# main.net
KiCad netlist of a schematic drawn in EAGLE
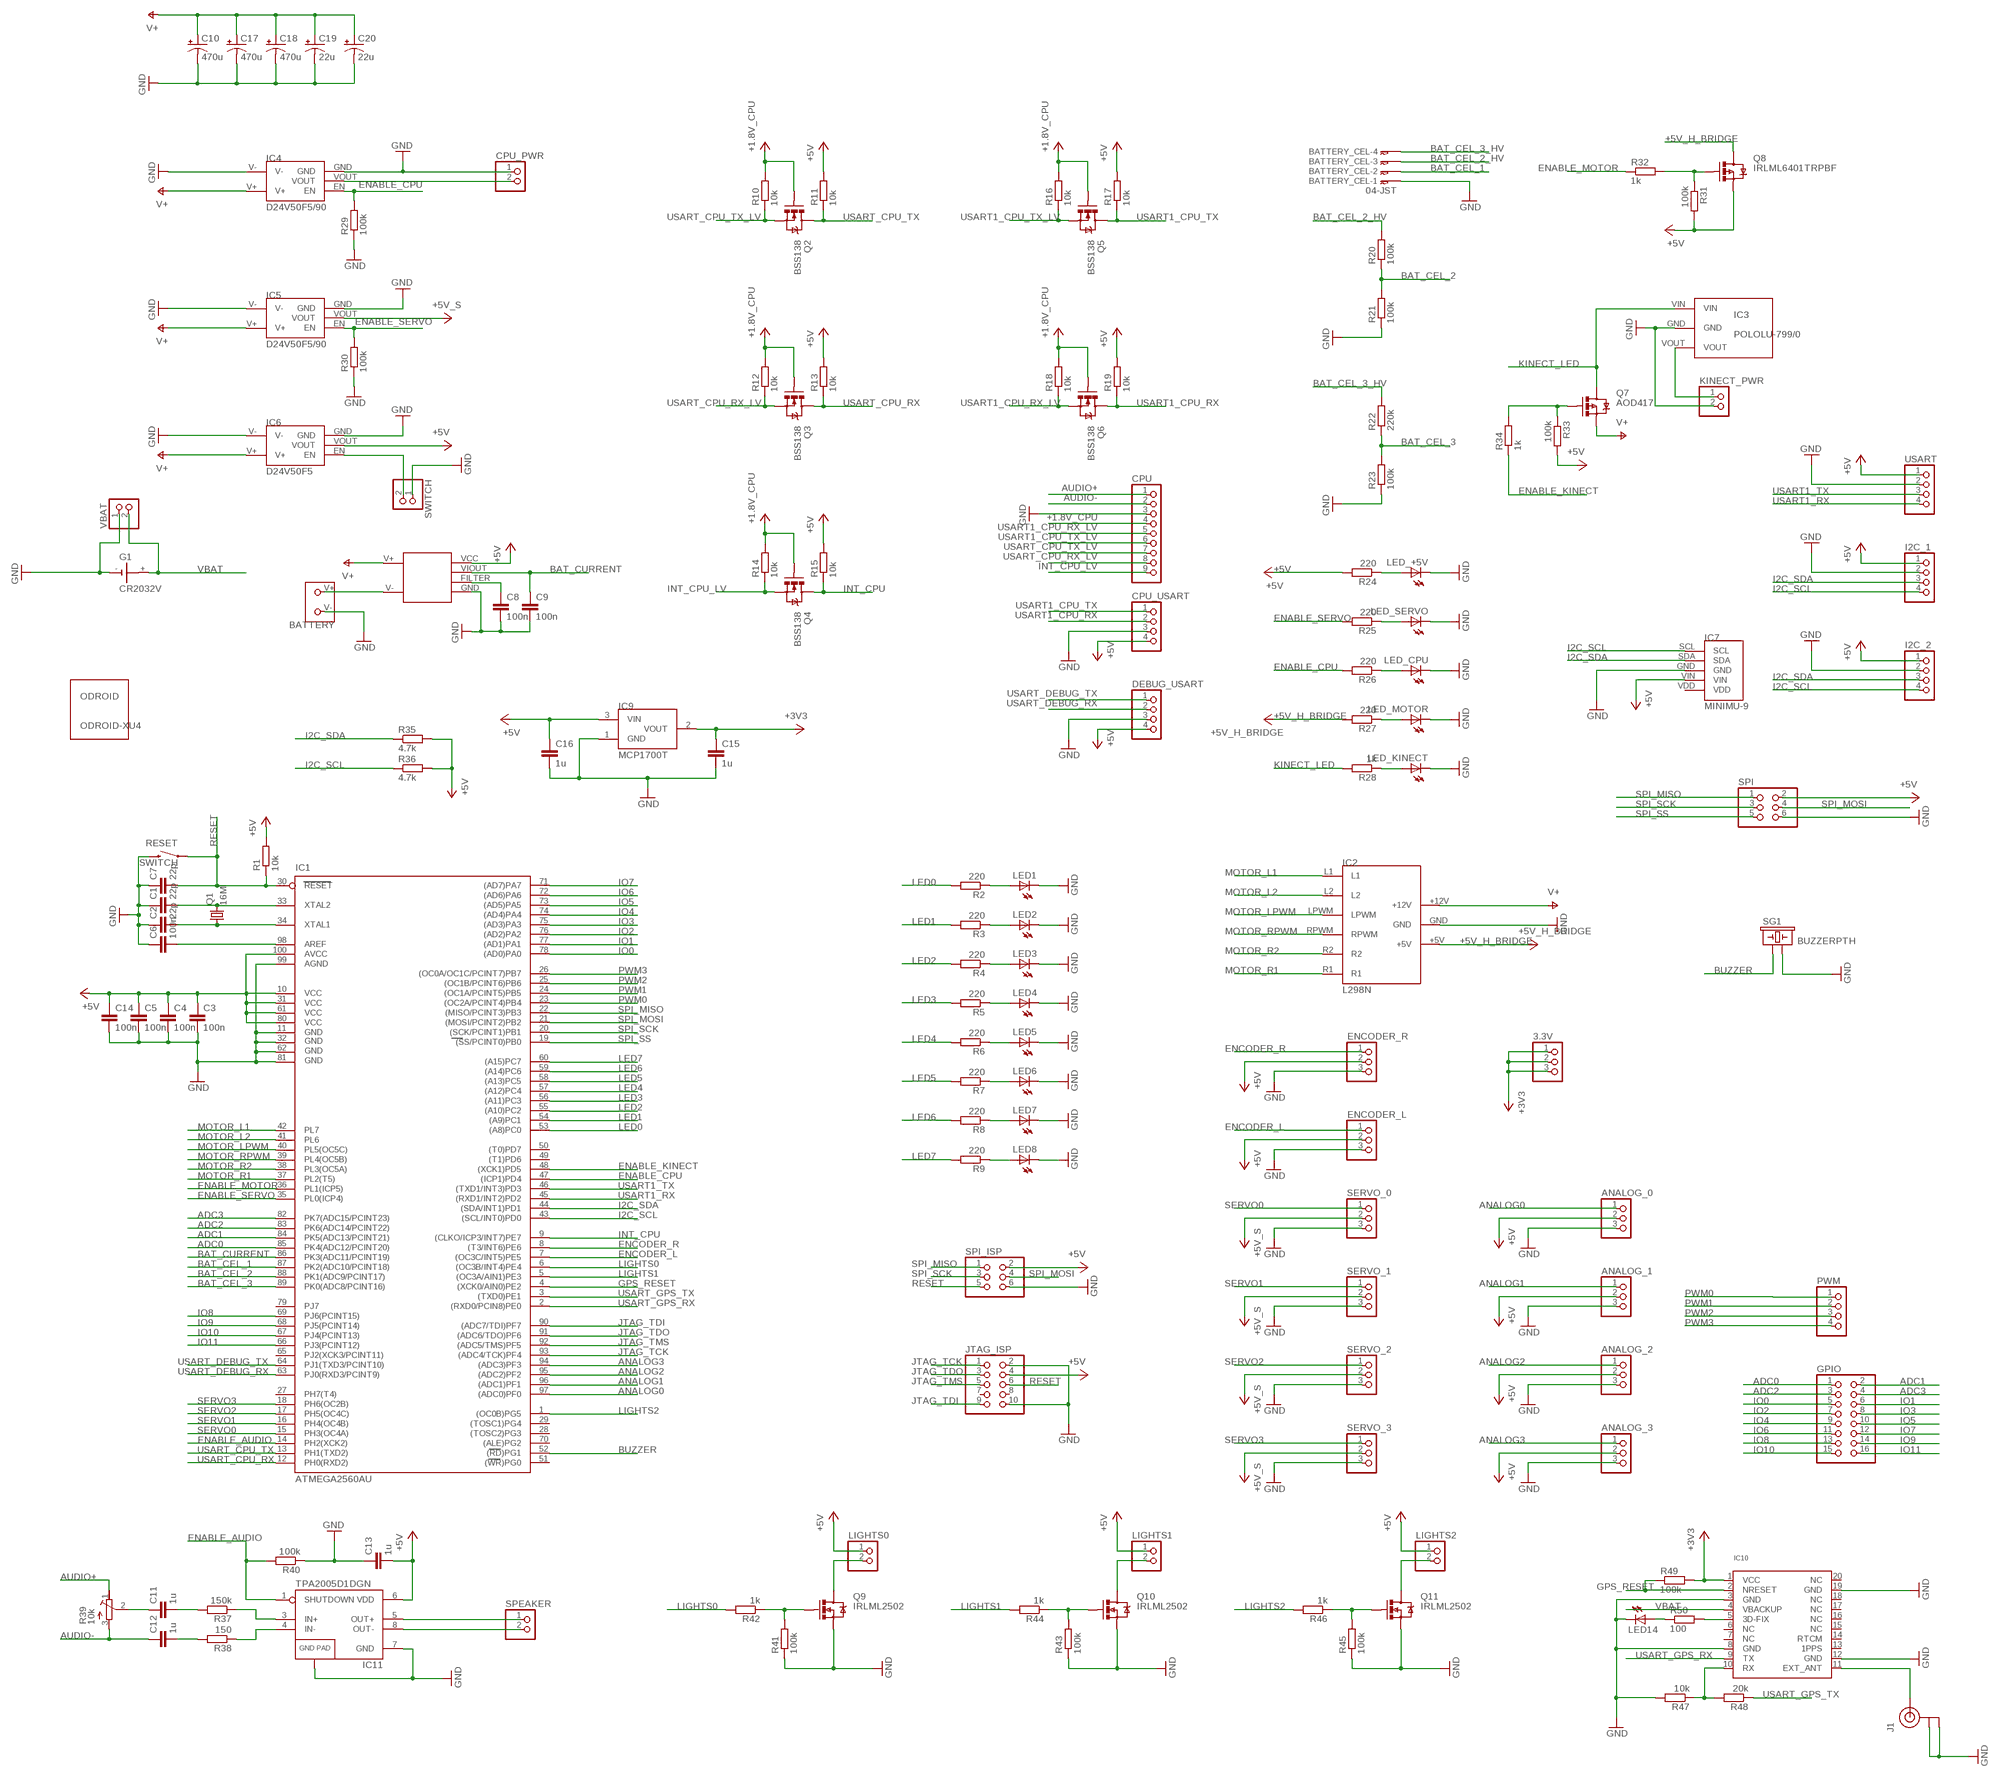
[diagram p0: schematic, sheet 1]

(export (version "E")
  (design (tool "Eeschema 10.0.6"))
  (components
    (comp (ref "3.3V")
      (value "PINHD-1X3")
      (footprint "eagle-import:1X03")
      (libsource (lib "eagle-import") (part "PINHD-1X3"))
    )
    (comp (ref "ANALOG_0")
      (value "PINHD-1X3")
      (footprint "eagle-import:1X03")
      (libsource (lib "eagle-import") (part "PINHD-1X3"))
    )
    (comp (ref "ANALOG_1")
      (value "PINHD-1X3")
      (footprint "eagle-import:1X03")
      (libsource (lib "eagle-import") (part "PINHD-1X3"))
    )
    (comp (ref "ANALOG_2")
      (value "PINHD-1X3")
      (footprint "eagle-import:1X03")
      (libsource (lib "eagle-import") (part "PINHD-1X3"))
    )
    (comp (ref "ANALOG_3")
      (value "PINHD-1X3")
      (footprint "eagle-import:1X03")
      (libsource (lib "eagle-import") (part "PINHD-1X3"))
    )
    (comp (ref "BATTERY")
      (value "XT60")
      (footprint "eagle-import:XT60")
      (libsource (lib "eagle-import") (part "XT60"))
    )
    (comp (ref "BATTERY_CEL")
      (value "04-JST")
      (footprint "eagle-import:B4B-XH")
      (libsource (lib "eagle-import") (part "04-JST-B4B-XH-A"))
    )
    (comp (ref "C1")
      (value "22p")
      (footprint "eagle-import:C0805")
      (libsource (lib "eagle-import") (part "C-EUC0805"))
    )
    (comp (ref "C2")
      (value "22p")
      (footprint "eagle-import:C0805")
      (libsource (lib "eagle-import") (part "C-EUC0805"))
    )
    (comp (ref "C3")
      (value "100n")
      (footprint "eagle-import:C0805")
      (libsource (lib "eagle-import") (part "C-EUC0805"))
    )
    (comp (ref "C4")
      (value "100n")
      (footprint "eagle-import:C0805")
      (libsource (lib "eagle-import") (part "C-EUC0805"))
    )
    (comp (ref "C5")
      (value "100n")
      (footprint "eagle-import:C0805")
      (libsource (lib "eagle-import") (part "C-EUC0805"))
    )
    (comp (ref "C6")
      (value "100n")
      (footprint "eagle-import:C0805")
      (libsource (lib "eagle-import") (part "C-EUC0805"))
    )
    (comp (ref "C7")
      (value "22p")
      (footprint "eagle-import:C0805")
      (libsource (lib "eagle-import") (part "C-EUC0805"))
    )
    (comp (ref "C8")
      (value "100n")
      (footprint "eagle-import:C0805")
      (libsource (lib "eagle-import") (part "C-EUC0805"))
    )
    (comp (ref "C9")
      (value "100n")
      (footprint "eagle-import:C0805")
      (libsource (lib "eagle-import") (part "C-EUC0805"))
    )
    (comp (ref "C10")
      (value "470u")
      (footprint "eagle-import:PANASONIC_G")
      (libsource (lib "eagle-import") (part "CAP_POLG"))
    )
    (comp (ref "C11")
      (value "1u")
      (footprint "eagle-import:C0805")
      (libsource (lib "eagle-import") (part "C-EUC0805"))
    )
    (comp (ref "C12")
      (value "1u")
      (footprint "eagle-import:C0805")
      (libsource (lib "eagle-import") (part "C-EUC0805"))
    )
    (comp (ref "C13")
      (value "1u")
      (footprint "eagle-import:C0805")
      (libsource (lib "eagle-import") (part "C-EUC0805"))
    )
    (comp (ref "C14")
      (value "100n")
      (footprint "eagle-import:C0805")
      (libsource (lib "eagle-import") (part "C-EUC0805"))
    )
    (comp (ref "C15")
      (value "1u")
      (footprint "eagle-import:C0805")
      (libsource (lib "eagle-import") (part "C-EUC0805"))
    )
    (comp (ref "C16")
      (value "1u")
      (footprint "eagle-import:C0805")
      (libsource (lib "eagle-import") (part "C-EUC0805"))
    )
    (comp (ref "C17")
      (value "470u")
      (footprint "eagle-import:PANASONIC_G")
      (libsource (lib "eagle-import") (part "CAP_POLG"))
    )
    (comp (ref "C18")
      (value "470u")
      (footprint "eagle-import:PANASONIC_G")
      (libsource (lib "eagle-import") (part "CAP_POLG"))
    )
    (comp (ref "C19")
      (value "22u")
      (footprint "eagle-import:EIA6032")
      (libsource (lib "eagle-import") (part "SparkFun-Passives_CAP_POL6032"))
    )
    (comp (ref "C20")
      (value "22u")
      (footprint "eagle-import:EIA6032")
      (libsource (lib "eagle-import") (part "SparkFun-Passives_CAP_POL6032"))
    )
    (comp (ref "CPU")
      (value "PINHD-1X9")
      (footprint "eagle-import:1X09")
      (libsource (lib "eagle-import") (part "PINHD-1X9"))
    )
    (comp (ref "CPU_PWR")
      (value "PINHD-1X2")
      (footprint "eagle-import:1X02")
      (libsource (lib "eagle-import") (part "PINHD-1X2"))
    )
    (comp (ref "CPU_USART")
      (value "PINHD-1X4/90")
      (footprint "eagle-import:1X04_90")
      (libsource (lib "eagle-import") (part "PINHD-1X4/90"))
    )
    (comp (ref "DEBUG_USART")
      (value "PINHD-1X4/90")
      (footprint "eagle-import:1X04_90")
      (libsource (lib "eagle-import") (part "PINHD-1X4/90"))
    )
    (comp (ref "ENCODER_L")
      (value "PINHD-1X3")
      (footprint "eagle-import:1X03")
      (libsource (lib "eagle-import") (part "PINHD-1X3"))
    )
    (comp (ref "ENCODER_R")
      (value "PINHD-1X3")
      (footprint "eagle-import:1X03")
      (libsource (lib "eagle-import") (part "PINHD-1X3"))
    )
    (comp (ref "G1")
      (value "CR2032V")
      (footprint "eagle-import:CR2032V")
      (libsource (lib "eagle-import") (part "CR2032V"))
    )
    (comp (ref "GPIO")
      (value "PINHD-2X8")
      (footprint "eagle-import:2X08")
      (libsource (lib "eagle-import") (part "PINHD-2X8"))
    )
    (comp (ref "I2C_1")
      (value "PINHD-1X4")
      (footprint "eagle-import:1X04")
      (libsource (lib "eagle-import") (part "PINHD-1X4"))
    )
    (comp (ref "I2C_2")
      (value "PINHD-1X4")
      (footprint "eagle-import:1X04")
      (libsource (lib "eagle-import") (part "PINHD-1X4"))
    )
    (comp (ref "IC1")
      (value "ATMEGA2560AU")
      (footprint "eagle-import:TQFP100")
      (libsource (lib "eagle-import") (part "ATMEGA2560AU"))
    )
    (comp (ref "IC2")
      (value "L298N")
      (footprint "eagle-import:L298N-MOD")
      (libsource (lib "eagle-import") (part "L298N"))
    )
    (comp (ref "IC3")
      (value "POLOLU-799/0")
      (footprint "eagle-import:POLOLU799_0")
      (libsource (lib "eagle-import") (part "POLOLU-799/0"))
    )
    (comp (ref "IC4")
      (value "D24V50F5/90")
      (footprint "eagle-import:D24V50_90")
      (libsource (lib "eagle-import") (part "D24V50F5/90"))
    )
    (comp (ref "IC5")
      (value "D24V50F5/90")
      (footprint "eagle-import:D24V50_90")
      (libsource (lib "eagle-import") (part "D24V50F5/90"))
    )
    (comp (ref "IC6")
      (value "D24V50F5")
      (footprint "eagle-import:D24V50")
      (libsource (lib "eagle-import") (part "D24V50F5"))
    )
    (comp (ref "IC7")
      (value "MINIMU-9")
      (footprint "eagle-import:MINIMU-9_V3")
      (libsource (lib "eagle-import") (part "MINIMU-9"))
    )
    (comp (ref "IC8")
      (value "ACS715")
      (footprint "eagle-import:ACS71X")
      (libsource (lib "eagle-import") (part "ACS715"))
    )
    (comp (ref "IC9")
      (value "MCP1700T")
      (footprint "eagle-import:SOT23")
      (libsource (lib "eagle-import") (part "MCP1700T"))
    )
    (comp (ref "IC10")
      (value "GPS_FGPMMOPA6H")
      (footprint "eagle-import:FGPMMOPA6H")
      (libsource (lib "eagle-import") (part "GPS_FGPMMOPA6H"))
    )
    (comp (ref "IC11")
      (value "TPA2005D1DGN")
      (footprint "eagle-import:POWER-SOP8")
      (libsource (lib "eagle-import") (part "TPA2005D1DGN"))
    )
    (comp (ref "J1")
      (value "U.FL")
      (footprint "eagle-import:U.FL")
      (libsource (lib "eagle-import") (part "U.FL"))
    )
    (comp (ref "JTAG_ISP")
      (value "PINHD-2X5/90")
      (footprint "eagle-import:2X05_90")
      (libsource (lib "eagle-import") (part "PINHD-2X5/90"))
    )
    (comp (ref "KINECT_PWR")
      (value "PINHD-1X2")
      (footprint "eagle-import:1X02")
      (libsource (lib "eagle-import") (part "PINHD-1X2"))
    )
    (comp (ref "LED1")
      (value "LEDCHIPLED_0805")
      (footprint "eagle-import:CHIPLED_0805")
      (libsource (lib "eagle-import") (part "LEDCHIPLED_0805"))
    )
    (comp (ref "LED2")
      (value "LEDCHIPLED_0805")
      (footprint "eagle-import:CHIPLED_0805")
      (libsource (lib "eagle-import") (part "LEDCHIPLED_0805"))
    )
    (comp (ref "LED3")
      (value "LEDCHIPLED_0805")
      (footprint "eagle-import:CHIPLED_0805")
      (libsource (lib "eagle-import") (part "LEDCHIPLED_0805"))
    )
    (comp (ref "LED4")
      (value "LEDCHIPLED_0805")
      (footprint "eagle-import:CHIPLED_0805")
      (libsource (lib "eagle-import") (part "LEDCHIPLED_0805"))
    )
    (comp (ref "LED5")
      (value "LEDCHIPLED_0805")
      (footprint "eagle-import:CHIPLED_0805")
      (libsource (lib "eagle-import") (part "LEDCHIPLED_0805"))
    )
    (comp (ref "LED6")
      (value "LEDCHIPLED_0805")
      (footprint "eagle-import:CHIPLED_0805")
      (libsource (lib "eagle-import") (part "LEDCHIPLED_0805"))
    )
    (comp (ref "LED7")
      (value "LEDCHIPLED_0805")
      (footprint "eagle-import:CHIPLED_0805")
      (libsource (lib "eagle-import") (part "LEDCHIPLED_0805"))
    )
    (comp (ref "LED8")
      (value "LEDCHIPLED_0805")
      (footprint "eagle-import:CHIPLED_0805")
      (libsource (lib "eagle-import") (part "LEDCHIPLED_0805"))
    )
    (comp (ref "LED14")
      (value "LEDCHIPLED_0805")
      (footprint "eagle-import:CHIPLED_0805")
      (libsource (lib "eagle-import") (part "LEDCHIPLED_0805"))
    )
    (comp (ref "LED_+5V")
      (value "LEDCHIPLED_0805")
      (footprint "eagle-import:CHIPLED_0805")
      (libsource (lib "eagle-import") (part "LEDCHIPLED_0805"))
    )
    (comp (ref "LED_CPU")
      (value "LEDCHIPLED_0805")
      (footprint "eagle-import:CHIPLED_0805")
      (libsource (lib "eagle-import") (part "LEDCHIPLED_0805"))
    )
    (comp (ref "LED_KINECT")
      (value "LEDCHIPLED_0805")
      (footprint "eagle-import:CHIPLED_0805")
      (libsource (lib "eagle-import") (part "LEDCHIPLED_0805"))
    )
    (comp (ref "LED_MOTOR")
      (value "LEDCHIPLED_0805")
      (footprint "eagle-import:CHIPLED_0805")
      (libsource (lib "eagle-import") (part "LEDCHIPLED_0805"))
    )
    (comp (ref "LED_SERVO")
      (value "LEDCHIPLED_0805")
      (footprint "eagle-import:CHIPLED_0805")
      (libsource (lib "eagle-import") (part "LEDCHIPLED_0805"))
    )
    (comp (ref "LIGHTS0")
      (value "PINHD-1X2")
      (footprint "eagle-import:1X02")
      (libsource (lib "eagle-import") (part "PINHD-1X2"))
    )
    (comp (ref "LIGHTS1")
      (value "PINHD-1X2")
      (footprint "eagle-import:1X02")
      (libsource (lib "eagle-import") (part "PINHD-1X2"))
    )
    (comp (ref "LIGHTS2")
      (value "PINHD-1X2")
      (footprint "eagle-import:1X02")
      (libsource (lib "eagle-import") (part "PINHD-1X2"))
    )
    (comp (ref "ODROID")
      (value "ODROID-XU4")
      (footprint "eagle-import:ODROID-XU4")
      (libsource (lib "eagle-import") (part "ODROID-XU4"))
    )
    (comp (ref "PWM")
      (value "PINHD-1X4")
      (footprint "eagle-import:1X04")
      (libsource (lib "eagle-import") (part "PINHD-1X4"))
    )
    (comp (ref "Q1")
      (value "16M")
      (footprint "eagle-import:CRYSTAL-TXC-7A")
      (libsource (lib "eagle-import") (part "CRYSTALTXC-7A"))
    )
    (comp (ref "Q2")
      (value "BSS138")
      (footprint "eagle-import:SOT23-3")
      (libsource (lib "eagle-import") (part "MOSFET-NCHANNELBSS138"))
    )
    (comp (ref "Q3")
      (value "BSS138")
      (footprint "eagle-import:SOT23-3")
      (libsource (lib "eagle-import") (part "MOSFET-NCHANNELBSS138"))
    )
    (comp (ref "Q4")
      (value "BSS138")
      (footprint "eagle-import:SOT23-3")
      (libsource (lib "eagle-import") (part "MOSFET-NCHANNELBSS138"))
    )
    (comp (ref "Q5")
      (value "BSS138")
      (footprint "eagle-import:SOT23-3")
      (libsource (lib "eagle-import") (part "MOSFET-NCHANNELBSS138"))
    )
    (comp (ref "Q6")
      (value "BSS138")
      (footprint "eagle-import:SOT23-3")
      (libsource (lib "eagle-import") (part "MOSFET-NCHANNELBSS138"))
    )
    (comp (ref "Q7")
      (value "AOD417")
      (footprint "eagle-import:TO252")
      (libsource (lib "eagle-import") (part "AOD417"))
    )
    (comp (ref "Q8")
      (value "IRLML6401TRPBF")
      (footprint "eagle-import:SOT23")
      (libsource (lib "eagle-import") (part "IRLML6401TRPBF"))
    )
    (comp (ref "Q9")
      (value "IRLML2502")
      (footprint "eagle-import:SOT23")
      (libsource (lib "eagle-import") (part "IRLML2502"))
    )
    (comp (ref "Q10")
      (value "IRLML2502")
      (footprint "eagle-import:SOT23")
      (libsource (lib "eagle-import") (part "IRLML2502"))
    )
    (comp (ref "Q11")
      (value "IRLML2502")
      (footprint "eagle-import:SOT23")
      (libsource (lib "eagle-import") (part "IRLML2502"))
    )
    (comp (ref "R1")
      (value "10k")
      (footprint "eagle-import:R0805")
      (libsource (lib "eagle-import") (part "R-EU_R0805"))
    )
    (comp (ref "R2")
      (value "220")
      (footprint "eagle-import:R0805")
      (libsource (lib "eagle-import") (part "R-EU_R0805"))
    )
    (comp (ref "R3")
      (value "220")
      (footprint "eagle-import:R0805")
      (libsource (lib "eagle-import") (part "R-EU_R0805"))
    )
    (comp (ref "R4")
      (value "220")
      (footprint "eagle-import:R0805")
      (libsource (lib "eagle-import") (part "R-EU_R0805"))
    )
    (comp (ref "R5")
      (value "220")
      (footprint "eagle-import:R0805")
      (libsource (lib "eagle-import") (part "R-EU_R0805"))
    )
    (comp (ref "R6")
      (value "220")
      (footprint "eagle-import:R0805")
      (libsource (lib "eagle-import") (part "R-EU_R0805"))
    )
    (comp (ref "R7")
      (value "220")
      (footprint "eagle-import:R0805")
      (libsource (lib "eagle-import") (part "R-EU_R0805"))
    )
    (comp (ref "R8")
      (value "220")
      (footprint "eagle-import:R0805")
      (libsource (lib "eagle-import") (part "R-EU_R0805"))
    )
    (comp (ref "R9")
      (value "220")
      (footprint "eagle-import:R0805")
      (libsource (lib "eagle-import") (part "R-EU_R0805"))
    )
    (comp (ref "R10")
      (value "10k")
      (footprint "eagle-import:R0805")
      (libsource (lib "eagle-import") (part "R-EU_R0805"))
    )
    (comp (ref "R11")
      (value "10k")
      (footprint "eagle-import:R0805")
      (libsource (lib "eagle-import") (part "R-EU_R0805"))
    )
    (comp (ref "R12")
      (value "10k")
      (footprint "eagle-import:R0805")
      (libsource (lib "eagle-import") (part "R-EU_R0805"))
    )
    (comp (ref "R13")
      (value "10k")
      (footprint "eagle-import:R0805")
      (libsource (lib "eagle-import") (part "R-EU_R0805"))
    )
    (comp (ref "R14")
      (value "10k")
      (footprint "eagle-import:R0805")
      (libsource (lib "eagle-import") (part "R-EU_R0805"))
    )
    (comp (ref "R15")
      (value "10k")
      (footprint "eagle-import:R0805")
      (libsource (lib "eagle-import") (part "R-EU_R0805"))
    )
    (comp (ref "R16")
      (value "10k")
      (footprint "eagle-import:R0805")
      (libsource (lib "eagle-import") (part "R-EU_R0805"))
    )
    (comp (ref "R17")
      (value "10k")
      (footprint "eagle-import:R0805")
      (libsource (lib "eagle-import") (part "R-EU_R0805"))
    )
    (comp (ref "R18")
      (value "10k")
      (footprint "eagle-import:R0805")
      (libsource (lib "eagle-import") (part "R-EU_R0805"))
    )
    (comp (ref "R19")
      (value "10k")
      (footprint "eagle-import:R0805")
      (libsource (lib "eagle-import") (part "R-EU_R0805"))
    )
    (comp (ref "R20")
      (value "100k")
      (footprint "eagle-import:R0805")
      (libsource (lib "eagle-import") (part "R-EU_R0805"))
    )
    (comp (ref "R21")
      (value "100k")
      (footprint "eagle-import:R0805")
      (libsource (lib "eagle-import") (part "R-EU_R0805"))
    )
    (comp (ref "R22")
      (value "220k")
      (footprint "eagle-import:R0805")
      (libsource (lib "eagle-import") (part "R-EU_R0805"))
    )
    (comp (ref "R23")
      (value "100k")
      (footprint "eagle-import:R0805")
      (libsource (lib "eagle-import") (part "R-EU_R0805"))
    )
    (comp (ref "R24")
      (value "220")
      (footprint "eagle-import:R0805")
      (libsource (lib "eagle-import") (part "R-EU_R0805"))
    )
    (comp (ref "R25")
      (value "220")
      (footprint "eagle-import:R0805")
      (libsource (lib "eagle-import") (part "R-EU_R0805"))
    )
    (comp (ref "R26")
      (value "220")
      (footprint "eagle-import:R0805")
      (libsource (lib "eagle-import") (part "R-EU_R0805"))
    )
    (comp (ref "R27")
      (value "220")
      (footprint "eagle-import:R0805")
      (libsource (lib "eagle-import") (part "R-EU_R0805"))
    )
    (comp (ref "R28")
      (value "1k")
      (footprint "eagle-import:R0805")
      (libsource (lib "eagle-import") (part "R-EU_R0805"))
    )
    (comp (ref "R29")
      (value "100k")
      (footprint "eagle-import:R0805")
      (libsource (lib "eagle-import") (part "R-EU_R0805"))
    )
    (comp (ref "R30")
      (value "100k")
      (footprint "eagle-import:R0805")
      (libsource (lib "eagle-import") (part "R-EU_R0805"))
    )
    (comp (ref "R31")
      (value "100k")
      (footprint "eagle-import:R0805")
      (libsource (lib "eagle-import") (part "R-EU_R0805"))
    )
    (comp (ref "R32")
      (value "1k")
      (footprint "eagle-import:R0805")
      (libsource (lib "eagle-import") (part "R-EU_R0805"))
    )
    (comp (ref "R33")
      (value "100k")
      (footprint "eagle-import:R0805")
      (libsource (lib "eagle-import") (part "R-EU_R0805"))
    )
    (comp (ref "R34")
      (value "1k")
      (footprint "eagle-import:R0805")
      (libsource (lib "eagle-import") (part "R-EU_R0805"))
    )
    (comp (ref "R35")
      (value "4.7k")
      (footprint "eagle-import:R0805")
      (libsource (lib "eagle-import") (part "R-EU_R0805"))
    )
    (comp (ref "R36")
      (value "4.7k")
      (footprint "eagle-import:R0805")
      (libsource (lib "eagle-import") (part "R-EU_R0805"))
    )
    (comp (ref "R37")
      (value "150k")
      (footprint "eagle-import:R0805")
      (libsource (lib "eagle-import") (part "R-EU_R0805"))
    )
    (comp (ref "R38")
      (value "150")
      (footprint "eagle-import:R0805")
      (libsource (lib "eagle-import") (part "R-EU_R0805"))
    )
    (comp (ref "R39")
      (value "10k")
      (footprint "eagle-import:RTRIM3314G")
      (libsource (lib "eagle-import") (part "R-TRIMM3314G"))
    )
    (comp (ref "R40")
      (value "100k")
      (footprint "eagle-import:R0805")
      (libsource (lib "eagle-import") (part "R-EU_R0805"))
    )
    (comp (ref "R41")
      (value "100k")
      (footprint "eagle-import:R0805")
      (libsource (lib "eagle-import") (part "R-EU_R0805"))
    )
    (comp (ref "R42")
      (value "1k")
      (footprint "eagle-import:R0805")
      (libsource (lib "eagle-import") (part "R-EU_R0805"))
    )
    (comp (ref "R43")
      (value "100k")
      (footprint "eagle-import:R0805")
      (libsource (lib "eagle-import") (part "R-EU_R0805"))
    )
    (comp (ref "R44")
      (value "1k")
      (footprint "eagle-import:R0805")
      (libsource (lib "eagle-import") (part "R-EU_R0805"))
    )
    (comp (ref "R45")
      (value "100k")
      (footprint "eagle-import:R0805")
      (libsource (lib "eagle-import") (part "R-EU_R0805"))
    )
    (comp (ref "R46")
      (value "1k")
      (footprint "eagle-import:R0805")
      (libsource (lib "eagle-import") (part "R-EU_R0805"))
    )
    (comp (ref "R47")
      (value "10k")
      (footprint "eagle-import:R0805")
      (libsource (lib "eagle-import") (part "R-EU_R0805"))
    )
    (comp (ref "R48")
      (value "20k")
      (footprint "eagle-import:R0805")
      (libsource (lib "eagle-import") (part "R-EU_R0805"))
    )
    (comp (ref "R49")
      (value "100k")
      (footprint "eagle-import:R0805")
      (libsource (lib "eagle-import") (part "R-EU_R0805"))
    )
    (comp (ref "R50")
      (value "100")
      (footprint "eagle-import:R0805")
      (libsource (lib "eagle-import") (part "R-EU_R0805"))
    )
    (comp (ref "RESET")
      (value "SWITCH")
      (footprint "eagle-import:TACTILE_SWITCH_TALL")
      (libsource (lib "eagle-import") (part "SWITCH-MOMENTARY-2SMD-4"))
    )
    (comp (ref "SERVO_0")
      (value "PINHD-1X3")
      (footprint "eagle-import:1X03")
      (libsource (lib "eagle-import") (part "PINHD-1X3"))
    )
    (comp (ref "SERVO_1")
      (value "PINHD-1X3")
      (footprint "eagle-import:1X03")
      (libsource (lib "eagle-import") (part "PINHD-1X3"))
    )
    (comp (ref "SERVO_2")
      (value "PINHD-1X3")
      (footprint "eagle-import:1X03")
      (libsource (lib "eagle-import") (part "PINHD-1X3"))
    )
    (comp (ref "SERVO_3")
      (value "PINHD-1X3")
      (footprint "eagle-import:1X03")
      (libsource (lib "eagle-import") (part "PINHD-1X3"))
    )
    (comp (ref "SG1")
      (value "BUZZERPTH")
      (footprint "eagle-import:BUZZER-12MM")
      (libsource (lib "eagle-import") (part "BUZZERPTH"))
    )
    (comp (ref "SPEAKER")
      (value "PINHD-1X2")
      (footprint "eagle-import:1X02")
      (libsource (lib "eagle-import") (part "PINHD-1X2"))
    )
    (comp (ref "SPI")
      (value "PINHD-2X3")
      (footprint "eagle-import:2X03")
      (libsource (lib "eagle-import") (part "PINHD-2X3"))
    )
    (comp (ref "SPI_ISP")
      (value "PINHD-2X3")
      (footprint "eagle-import:2X03")
      (libsource (lib "eagle-import") (part "PINHD-2X3"))
    )
    (comp (ref "SWITCH")
      (value "PINHD-1X2/90")
      (footprint "eagle-import:1X02_90")
      (libsource (lib "eagle-import") (part "PINHD-1X2/90"))
    )
    (comp (ref "USART")
      (value "PINHD-1X4")
      (footprint "eagle-import:1X04")
      (libsource (lib "eagle-import") (part "PINHD-1X4"))
    )
    (comp (ref "VBAT")
      (value "PINHD-1X2")
      (footprint "eagle-import:1X02")
      (libsource (lib "eagle-import") (part "PINHD-1X2"))
    )
  )
  (nets
    (net (code "1") (name "+1.8V_CPU") (class "Default")
      (node (ref "CPU") (pin "4") (pinfunction "4_4") (pintype "passive"))
      (node (ref "Q2") (pin "1") (pinfunction "G_1") (pintype "passive"))
      (node (ref "Q3") (pin "1") (pinfunction "G_1") (pintype "passive"))
      (node (ref "Q4") (pin "1") (pinfunction "G_1") (pintype "passive"))
      (node (ref "Q5") (pin "1") (pinfunction "G_1") (pintype "passive"))
      (node (ref "Q6") (pin "1") (pinfunction "G_1") (pintype "passive"))
      (node (ref "R10") (pin "2") (pinfunction "2_2") (pintype "passive"))
      (node (ref "R12") (pin "2") (pinfunction "2_2") (pintype "passive"))
      (node (ref "R14") (pin "2") (pinfunction "2_2") (pintype "passive"))
      (node (ref "R16") (pin "2") (pinfunction "2_2") (pintype "passive"))
      (node (ref "R18") (pin "2") (pinfunction "2_2") (pintype "passive"))
    )
    (net (code "2") (name "+3V3") (class "Default")
      (node (ref "3.3V") (pin "1") (pinfunction "1_1") (pintype "passive"))
      (node (ref "3.3V") (pin "2") (pinfunction "2_2") (pintype "passive"))
      (node (ref "3.3V") (pin "3") (pinfunction "3_3") (pintype "passive"))
      (node (ref "C15") (pin "1") (pinfunction "1_1") (pintype "passive"))
      (node (ref "IC10") (pin "1") (pinfunction "VCC_1") (pintype "bidirectional"))
      (node (ref "IC9") (pin "2") (pinfunction "VOUT_2") (pintype "power_in"))
      (node (ref "R49") (pin "2") (pinfunction "2_2") (pintype "passive"))
    )
    (net (code "3") (name "+5V") (class "Default")
      (node (ref "ANALOG_0") (pin "2") (pinfunction "2_2") (pintype "passive"))
      (node (ref "ANALOG_1") (pin "2") (pinfunction "2_2") (pintype "passive"))
      (node (ref "ANALOG_2") (pin "2") (pinfunction "2_2") (pintype "passive"))
      (node (ref "ANALOG_3") (pin "2") (pinfunction "2_2") (pintype "passive"))
      (node (ref "C13") (pin "2") (pinfunction "2_2") (pintype "passive"))
      (node (ref "C14") (pin "1") (pinfunction "1_1") (pintype "passive"))
      (node (ref "C16") (pin "1") (pinfunction "1_1") (pintype "passive"))
      (node (ref "C3") (pin "1") (pinfunction "1_1") (pintype "passive"))
      (node (ref "C4") (pin "1") (pinfunction "1_1") (pintype "passive"))
      (node (ref "C5") (pin "1") (pinfunction "1_1") (pintype "passive"))
      (node (ref "CPU_USART") (pin "4") (pinfunction "4_4") (pintype "passive"))
      (node (ref "DEBUG_USART") (pin "4") (pinfunction "4_4") (pintype "passive"))
      (node (ref "ENCODER_L") (pin "2") (pinfunction "2_2") (pintype "passive"))
      (node (ref "ENCODER_R") (pin "2") (pinfunction "2_2") (pintype "passive"))
      (node (ref "I2C_1") (pin "1") (pinfunction "1_1") (pintype "passive"))
      (node (ref "I2C_2") (pin "1") (pinfunction "1_1") (pintype "passive"))
      (node (ref "IC1") (pin "10") (pinfunction "VCC_10") (pintype "power_in"))
      (node (ref "IC1") (pin "100") (pinfunction "AVCC_100") (pintype "power_in"))
      (node (ref "IC1") (pin "31") (pinfunction "VCC1_31") (pintype "power_in"))
      (node (ref "IC1") (pin "61") (pinfunction "VCC2_61") (pintype "power_in"))
      (node (ref "IC1") (pin "80") (pinfunction "VCC3_80") (pintype "power_in"))
      (node (ref "IC11") (pin "6") (pinfunction "VDD_6") (pintype "power_in"))
      (node (ref "IC6") (pin "VOUT") (pinfunction "VOUT_VOUT") (pintype "bidirectional"))
      (node (ref "IC7") (pin "VIN") (pinfunction "VIN_VIN") (pintype "bidirectional"))
      (node (ref "IC8") (pin "VCC") (pinfunction "VCC_VCC") (pintype "bidirectional"))
      (node (ref "IC9") (pin "3") (pinfunction "VIN_3") (pintype "input"))
      (node (ref "JTAG_ISP") (pin "4") (pinfunction "4_4") (pintype "passive"))
      (node (ref "LIGHTS0") (pin "1") (pinfunction "1_1") (pintype "passive"))
      (node (ref "LIGHTS1") (pin "1") (pinfunction "1_1") (pintype "passive"))
      (node (ref "LIGHTS2") (pin "1") (pinfunction "1_1") (pintype "passive"))
      (node (ref "Q8") (pin "2") (pinfunction "S_2") (pintype "passive"))
      (node (ref "R1") (pin "2") (pinfunction "2_2") (pintype "passive"))
      (node (ref "R11") (pin "2") (pinfunction "2_2") (pintype "passive"))
      (node (ref "R13") (pin "2") (pinfunction "2_2") (pintype "passive"))
      (node (ref "R15") (pin "2") (pinfunction "2_2") (pintype "passive"))
      (node (ref "R17") (pin "2") (pinfunction "2_2") (pintype "passive"))
      (node (ref "R19") (pin "2") (pinfunction "2_2") (pintype "passive"))
      (node (ref "R24") (pin "2") (pinfunction "2_2") (pintype "passive"))
      (node (ref "R31") (pin "2") (pinfunction "2_2") (pintype "passive"))
      (node (ref "R33") (pin "2") (pinfunction "2_2") (pintype "passive"))
      (node (ref "R35") (pin "2") (pinfunction "2_2") (pintype "passive"))
      (node (ref "R36") (pin "2") (pinfunction "2_2") (pintype "passive"))
      (node (ref "SPI") (pin "2") (pinfunction "2_2") (pintype "passive"))
      (node (ref "SPI_ISP") (pin "2") (pinfunction "2_2") (pintype "passive"))
      (node (ref "USART") (pin "1") (pinfunction "1_1") (pintype "passive"))
    )
    (net (code "4") (name "+5V_H_BRIDGE") (class "Default")
      (node (ref "IC2") (pin "+5V") (pinfunction "+5V_+5V") (pintype "bidirectional"))
      (node (ref "Q8") (pin "3") (pinfunction "D_3") (pintype "passive"))
      (node (ref "R27") (pin "2") (pinfunction "2_2") (pintype "passive"))
    )
    (net (code "5") (name "+5V_S") (class "Default")
      (node (ref "IC5") (pin "VOUT") (pinfunction "VOUT_VOUT") (pintype "bidirectional"))
      (node (ref "SERVO_0") (pin "2") (pinfunction "2_2") (pintype "passive"))
      (node (ref "SERVO_1") (pin "2") (pinfunction "2_2") (pintype "passive"))
      (node (ref "SERVO_2") (pin "2") (pinfunction "2_2") (pintype "passive"))
      (node (ref "SERVO_3") (pin "2") (pinfunction "2_2") (pintype "passive"))
    )
    (net (code "6") (name "/ADC0") (class "Default")
      (node (ref "GPIO") (pin "1") (pinfunction "1_1") (pintype "passive"))
      (node (ref "IC1") (pin "85") (pinfunction "PK4(ADC12/PCINT20)_85") (pintype "bidirectional"))
    )
    (net (code "7") (name "/ADC1") (class "Default")
      (node (ref "GPIO") (pin "2") (pinfunction "2_2") (pintype "passive"))
      (node (ref "IC1") (pin "84") (pinfunction "PK5(ADC13/PCINT21)_84") (pintype "bidirectional"))
    )
    (net (code "8") (name "/ADC2") (class "Default")
      (node (ref "GPIO") (pin "3") (pinfunction "3_3") (pintype "passive"))
      (node (ref "IC1") (pin "83") (pinfunction "PK6(ADC14/PCINT22)_83") (pintype "bidirectional"))
    )
    (net (code "9") (name "/ADC3") (class "Default")
      (node (ref "GPIO") (pin "4") (pinfunction "4_4") (pintype "passive"))
      (node (ref "IC1") (pin "82") (pinfunction "PK7(ADC15/PCINT23)_82") (pintype "bidirectional"))
    )
    (net (code "10") (name "/ANALOG0") (class "Default")
      (node (ref "ANALOG_0") (pin "1") (pinfunction "1_1") (pintype "passive"))
      (node (ref "IC1") (pin "97") (pinfunction "(ADC0)PF0_97") (pintype "bidirectional"))
    )
    (net (code "11") (name "/ANALOG1") (class "Default")
      (node (ref "ANALOG_1") (pin "1") (pinfunction "1_1") (pintype "passive"))
      (node (ref "IC1") (pin "96") (pinfunction "(ADC1)PF1_96") (pintype "bidirectional"))
    )
    (net (code "12") (name "/ANALOG2") (class "Default")
      (node (ref "ANALOG_2") (pin "1") (pinfunction "1_1") (pintype "passive"))
      (node (ref "IC1") (pin "95") (pinfunction "(ADC2)PF2_95") (pintype "bidirectional"))
    )
    (net (code "13") (name "/ANALOG3") (class "Default")
      (node (ref "ANALOG_3") (pin "1") (pinfunction "1_1") (pintype "passive"))
      (node (ref "IC1") (pin "94") (pinfunction "(ADC3)PF3_94") (pintype "bidirectional"))
    )
    (net (code "14") (name "/AUDIO+") (class "Default")
      (node (ref "CPU") (pin "1") (pinfunction "1_1") (pintype "passive"))
      (node (ref "R39") (pin "1") (pinfunction "E_1") (pintype "passive"))
    )
    (net (code "15") (name "/AUDIO-") (class "Default")
      (node (ref "C12") (pin "1") (pinfunction "1_1") (pintype "passive"))
      (node (ref "CPU") (pin "2") (pinfunction "2_2") (pintype "passive"))
      (node (ref "R39") (pin "3") (pinfunction "A_3") (pintype "passive"))
    )
    (net (code "16") (name "/BAT_CEL_1") (class "Default")
      (node (ref "BATTERY_CEL") (pin "P$2") (pinfunction "1_P$2") (pintype "passive"))
      (node (ref "IC1") (pin "87") (pinfunction "PK2(ADC10/PCINT18)_87") (pintype "bidirectional"))
    )
    (net (code "17") (name "/BAT_CEL_2") (class "Default")
      (node (ref "IC1") (pin "88") (pinfunction "PK1(ADC9/PCINT17)_88") (pintype "bidirectional"))
      (node (ref "R20") (pin "1") (pinfunction "1_1") (pintype "passive"))
      (node (ref "R21") (pin "2") (pinfunction "2_2") (pintype "passive"))
    )
    (net (code "18") (name "/BAT_CEL_2_HV") (class "Default")
      (node (ref "BATTERY_CEL") (pin "P$3") (pinfunction "1_P$3") (pintype "passive"))
      (node (ref "R20") (pin "2") (pinfunction "2_2") (pintype "passive"))
    )
    (net (code "19") (name "/BAT_CEL_3") (class "Default")
      (node (ref "IC1") (pin "89") (pinfunction "PK0(ADC8/PCINT16)_89") (pintype "bidirectional"))
      (node (ref "R22") (pin "1") (pinfunction "1_1") (pintype "passive"))
      (node (ref "R23") (pin "2") (pinfunction "2_2") (pintype "passive"))
    )
    (net (code "20") (name "/BAT_CEL_3_HV") (class "Default")
      (node (ref "BATTERY_CEL") (pin "P$4") (pinfunction "1_P$4") (pintype "passive"))
      (node (ref "R22") (pin "2") (pinfunction "2_2") (pintype "passive"))
    )
    (net (code "21") (name "/BAT_CURRENT") (class "Default")
      (node (ref "C9") (pin "1") (pinfunction "1_1") (pintype "passive"))
      (node (ref "IC1") (pin "86") (pinfunction "PK3(ADC11/PCINT19)_86") (pintype "bidirectional"))
      (node (ref "IC8") (pin "VIOUT") (pinfunction "VIOUT_VIOUT") (pintype "bidirectional"))
    )
    (net (code "22") (name "/BUZZER") (class "Default")
      (node (ref "IC1") (pin "52") (pinfunction "(RD)PG1_52") (pintype "bidirectional"))
      (node (ref "SG1") (pin "+") (pinfunction "1_+") (pintype "passive"))
    )
    (net (code "23") (name "/ENABLE_AUDIO") (class "Default")
      (node (ref "IC1") (pin "14") (pinfunction "PH2(XCK2)_14") (pintype "bidirectional"))
      (node (ref "IC11") (pin "1") (pinfunction "SHUTDOWN_1") (pintype "input"))
      (node (ref "R40") (pin "2") (pinfunction "2_2") (pintype "passive"))
    )
    (net (code "24") (name "/ENABLE_CPU") (class "Default")
      (node (ref "IC1") (pin "47") (pinfunction "(ICP1)PD4_47") (pintype "bidirectional"))
      (node (ref "IC4") (pin "EN") (pinfunction "EN_EN") (pintype "bidirectional"))
      (node (ref "R26") (pin "2") (pinfunction "2_2") (pintype "passive"))
      (node (ref "R29") (pin "2") (pinfunction "2_2") (pintype "passive"))
    )
    (net (code "25") (name "/ENABLE_KINECT") (class "Default")
      (node (ref "IC1") (pin "48") (pinfunction "(XCK1)PD5_48") (pintype "bidirectional"))
      (node (ref "R34") (pin "1") (pinfunction "1_1") (pintype "passive"))
    )
    (net (code "26") (name "/ENABLE_MOTOR") (class "Default")
      (node (ref "IC1") (pin "36") (pinfunction "PL1(ICP5)_36") (pintype "bidirectional"))
      (node (ref "R32") (pin "1") (pinfunction "1_1") (pintype "passive"))
    )
    (net (code "27") (name "/ENABLE_SERVO") (class "Default")
      (node (ref "IC1") (pin "35") (pinfunction "PL0(ICP4)_35") (pintype "bidirectional"))
      (node (ref "IC5") (pin "EN") (pinfunction "EN_EN") (pintype "bidirectional"))
      (node (ref "R25") (pin "2") (pinfunction "2_2") (pintype "passive"))
      (node (ref "R30") (pin "2") (pinfunction "2_2") (pintype "passive"))
    )
    (net (code "28") (name "/ENCODER_L") (class "Default")
      (node (ref "ENCODER_L") (pin "1") (pinfunction "1_1") (pintype "passive"))
      (node (ref "IC1") (pin "7") (pinfunction "(OC3C/INT5)PE5_7") (pintype "bidirectional"))
    )
    (net (code "29") (name "/ENCODER_R") (class "Default")
      (node (ref "ENCODER_R") (pin "1") (pinfunction "1_1") (pintype "passive"))
      (node (ref "IC1") (pin "8") (pinfunction "(T3/INT6)PE6_8") (pintype "bidirectional"))
    )
    (net (code "30") (name "/GPS_RESET") (class "Default")
      (node (ref "IC1") (pin "4") (pinfunction "(XCK0/AIN0)PE2_4") (pintype "bidirectional"))
      (node (ref "IC10") (pin "2") (pinfunction "NRESET_2") (pintype "bidirectional"))
      (node (ref "R49") (pin "1") (pinfunction "1_1") (pintype "passive"))
    )
    (net (code "31") (name "/I2C_SCL") (class "Default")
      (node (ref "I2C_1") (pin "4") (pinfunction "4_4") (pintype "passive"))
      (node (ref "I2C_2") (pin "4") (pinfunction "4_4") (pintype "passive"))
      (node (ref "IC1") (pin "43") (pinfunction "(SCL/INT0)PD0_43") (pintype "bidirectional"))
      (node (ref "IC7") (pin "SCL") (pinfunction "SCL_SCL") (pintype "bidirectional"))
      (node (ref "R36") (pin "1") (pinfunction "1_1") (pintype "passive"))
    )
    (net (code "32") (name "/I2C_SDA") (class "Default")
      (node (ref "I2C_1") (pin "3") (pinfunction "3_3") (pintype "passive"))
      (node (ref "I2C_2") (pin "3") (pinfunction "3_3") (pintype "passive"))
      (node (ref "IC1") (pin "44") (pinfunction "(SDA/INT1)PD1_44") (pintype "bidirectional"))
      (node (ref "IC7") (pin "SDA") (pinfunction "SDA_SDA") (pintype "bidirectional"))
      (node (ref "R35") (pin "1") (pinfunction "1_1") (pintype "passive"))
    )
    (net (code "33") (name "/INT_CPU") (class "Default")
      (node (ref "IC1") (pin "9") (pinfunction "(CLKO/ICP3/INT7)PE7_9") (pintype "bidirectional"))
      (node (ref "Q4") (pin "3") (pinfunction "D_3") (pintype "passive"))
      (node (ref "R15") (pin "1") (pinfunction "1_1") (pintype "passive"))
    )
    (net (code "34") (name "/INT_CPU_LV") (class "Default")
      (node (ref "CPU") (pin "9") (pinfunction "9_9") (pintype "passive"))
      (node (ref "Q4") (pin "2") (pinfunction "S_2") (pintype "passive"))
      (node (ref "R14") (pin "1") (pinfunction "1_1") (pintype "passive"))
    )
    (net (code "35") (name "/IO0") (class "Default")
      (node (ref "GPIO") (pin "5") (pinfunction "5_5") (pintype "passive"))
      (node (ref "IC1") (pin "78") (pinfunction "(AD0)PA0_78") (pintype "bidirectional"))
    )
    (net (code "36") (name "/IO1") (class "Default")
      (node (ref "GPIO") (pin "6") (pinfunction "6_6") (pintype "passive"))
      (node (ref "IC1") (pin "77") (pinfunction "(AD1)PA1_77") (pintype "bidirectional"))
    )
    (net (code "37") (name "/IO2") (class "Default")
      (node (ref "GPIO") (pin "7") (pinfunction "7_7") (pintype "passive"))
      (node (ref "IC1") (pin "76") (pinfunction "(AD2)PA2_76") (pintype "bidirectional"))
    )
    (net (code "38") (name "/IO3") (class "Default")
      (node (ref "GPIO") (pin "8") (pinfunction "8_8") (pintype "passive"))
      (node (ref "IC1") (pin "75") (pinfunction "(AD3)PA3_75") (pintype "bidirectional"))
    )
    (net (code "39") (name "/IO4") (class "Default")
      (node (ref "GPIO") (pin "9") (pinfunction "9_9") (pintype "passive"))
      (node (ref "IC1") (pin "74") (pinfunction "(AD4)PA4_74") (pintype "bidirectional"))
    )
    (net (code "40") (name "/IO5") (class "Default")
      (node (ref "GPIO") (pin "10") (pinfunction "10_10") (pintype "passive"))
      (node (ref "IC1") (pin "73") (pinfunction "(AD5)PA5_73") (pintype "bidirectional"))
    )
    (net (code "41") (name "/IO6") (class "Default")
      (node (ref "GPIO") (pin "11") (pinfunction "11_11") (pintype "passive"))
      (node (ref "IC1") (pin "72") (pinfunction "(AD6)PA6_72") (pintype "bidirectional"))
    )
    (net (code "42") (name "/IO7") (class "Default")
      (node (ref "GPIO") (pin "12") (pinfunction "12_12") (pintype "passive"))
      (node (ref "IC1") (pin "71") (pinfunction "(AD7)PA7_71") (pintype "bidirectional"))
    )
    (net (code "43") (name "/IO8") (class "Default")
      (node (ref "GPIO") (pin "13") (pinfunction "13_13") (pintype "passive"))
      (node (ref "IC1") (pin "69") (pinfunction "PJ6(PCINT15)_69") (pintype "bidirectional"))
    )
    (net (code "44") (name "/IO9") (class "Default")
      (node (ref "GPIO") (pin "14") (pinfunction "14_14") (pintype "passive"))
      (node (ref "IC1") (pin "68") (pinfunction "PJ5(PCINT14)_68") (pintype "bidirectional"))
    )
    (net (code "45") (name "/IO10") (class "Default")
      (node (ref "GPIO") (pin "15") (pinfunction "15_15") (pintype "passive"))
      (node (ref "IC1") (pin "67") (pinfunction "PJ4(PCINT13)_67") (pintype "bidirectional"))
    )
    (net (code "46") (name "/IO11") (class "Default")
      (node (ref "GPIO") (pin "16") (pinfunction "16_16") (pintype "passive"))
      (node (ref "IC1") (pin "66") (pinfunction "PJ3(PCINT12)_66") (pintype "bidirectional"))
    )
    (net (code "47") (name "/JTAG_TCK") (class "Default")
      (node (ref "IC1") (pin "93") (pinfunction "(ADC4/TCK)PF4_93") (pintype "bidirectional"))
      (node (ref "JTAG_ISP") (pin "1") (pinfunction "1_1") (pintype "passive"))
    )
    (net (code "48") (name "/JTAG_TDI") (class "Default")
      (node (ref "IC1") (pin "90") (pinfunction "(ADC7/TDI)PF7_90") (pintype "bidirectional"))
      (node (ref "JTAG_ISP") (pin "9") (pinfunction "9_9") (pintype "passive"))
    )
    (net (code "49") (name "/JTAG_TDO") (class "Default")
      (node (ref "IC1") (pin "91") (pinfunction "(ADC6/TDO)PF6_91") (pintype "bidirectional"))
      (node (ref "JTAG_ISP") (pin "3") (pinfunction "3_3") (pintype "passive"))
    )
    (net (code "50") (name "/JTAG_TMS") (class "Default")
      (node (ref "IC1") (pin "92") (pinfunction "(ADC5/TMS)PF5_92") (pintype "bidirectional"))
      (node (ref "JTAG_ISP") (pin "5") (pinfunction "5_5") (pintype "passive"))
    )
    (net (code "51") (name "/KINECT_LED") (class "Default")
      (node (ref "IC3") (pin "VIN") (pinfunction "VIN_VIN") (pintype "bidirectional"))
      (node (ref "Q7") (pin "3") (pinfunction "D_3") (pintype "passive"))
      (node (ref "R28") (pin "2") (pinfunction "2_2") (pintype "passive"))
    )
    (net (code "52") (name "/LED0") (class "Default")
      (node (ref "IC1") (pin "53") (pinfunction "(A8)PC0_53") (pintype "bidirectional"))
      (node (ref "R2") (pin "2") (pinfunction "2_2") (pintype "passive"))
    )
    (net (code "53") (name "/LED1") (class "Default")
      (node (ref "IC1") (pin "54") (pinfunction "(A9)PC1_54") (pintype "bidirectional"))
      (node (ref "R3") (pin "2") (pinfunction "2_2") (pintype "passive"))
    )
    (net (code "54") (name "/LED2") (class "Default")
      (node (ref "IC1") (pin "55") (pinfunction "(A10)PC2_55") (pintype "bidirectional"))
      (node (ref "R4") (pin "2") (pinfunction "2_2") (pintype "passive"))
    )
    (net (code "55") (name "/LED3") (class "Default")
      (node (ref "IC1") (pin "56") (pinfunction "(A11)PC3_56") (pintype "bidirectional"))
      (node (ref "R5") (pin "2") (pinfunction "2_2") (pintype "passive"))
    )
    (net (code "56") (name "/LED4") (class "Default")
      (node (ref "IC1") (pin "57") (pinfunction "(A12)PC4_57") (pintype "bidirectional"))
      (node (ref "R6") (pin "2") (pinfunction "2_2") (pintype "passive"))
    )
    (net (code "57") (name "/LED5") (class "Default")
      (node (ref "IC1") (pin "58") (pinfunction "(A13)PC5_58") (pintype "bidirectional"))
      (node (ref "R7") (pin "2") (pinfunction "2_2") (pintype "passive"))
    )
    (net (code "58") (name "/LED6") (class "Default")
      (node (ref "IC1") (pin "59") (pinfunction "(A14)PC6_59") (pintype "bidirectional"))
      (node (ref "R8") (pin "2") (pinfunction "2_2") (pintype "passive"))
    )
    (net (code "59") (name "/LED7") (class "Default")
      (node (ref "IC1") (pin "60") (pinfunction "(A15)PC7_60") (pintype "bidirectional"))
      (node (ref "R9") (pin "2") (pinfunction "2_2") (pintype "passive"))
    )
    (net (code "60") (name "/LIGHTS0") (class "Default")
      (node (ref "IC1") (pin "6") (pinfunction "(OC3B/INT4)PE4_6") (pintype "bidirectional"))
      (node (ref "R42") (pin "2") (pinfunction "2_2") (pintype "passive"))
    )
    (net (code "61") (name "/LIGHTS1") (class "Default")
      (node (ref "IC1") (pin "5") (pinfunction "(OC3A/AIN1)PE3_5") (pintype "bidirectional"))
      (node (ref "R44") (pin "2") (pinfunction "2_2") (pintype "passive"))
    )
    (net (code "62") (name "/LIGHTS2") (class "Default")
      (node (ref "IC1") (pin "1") (pinfunction "(OC0B)PG5_1") (pintype "bidirectional"))
      (node (ref "R46") (pin "2") (pinfunction "2_2") (pintype "passive"))
    )
    (net (code "63") (name "/MOTOR_L1") (class "Default")
      (node (ref "IC1") (pin "42") (pinfunction "PL7_42") (pintype "bidirectional"))
      (node (ref "IC2") (pin "L1") (pinfunction "L1_L1") (pintype "bidirectional"))
    )
    (net (code "64") (name "/MOTOR_L2") (class "Default")
      (node (ref "IC1") (pin "41") (pinfunction "PL6_41") (pintype "bidirectional"))
      (node (ref "IC2") (pin "L2") (pinfunction "L2_L2") (pintype "bidirectional"))
    )
    (net (code "65") (name "/MOTOR_LPWM") (class "Default")
      (node (ref "IC1") (pin "40") (pinfunction "PL5(OC5C)_40") (pintype "bidirectional"))
      (node (ref "IC2") (pin "LPWM") (pinfunction "LPWM_LPWM") (pintype "bidirectional"))
    )
    (net (code "66") (name "/MOTOR_R1") (class "Default")
      (node (ref "IC1") (pin "37") (pinfunction "PL2(T5)_37") (pintype "bidirectional"))
      (node (ref "IC2") (pin "R1") (pinfunction "R1_R1") (pintype "bidirectional"))
    )
    (net (code "67") (name "/MOTOR_R2") (class "Default")
      (node (ref "IC1") (pin "38") (pinfunction "PL3(OC5A)_38") (pintype "bidirectional"))
      (node (ref "IC2") (pin "R2") (pinfunction "R2_R2") (pintype "bidirectional"))
    )
    (net (code "68") (name "/MOTOR_RPWM") (class "Default")
      (node (ref "IC1") (pin "39") (pinfunction "PL4(OC5B)_39") (pintype "bidirectional"))
      (node (ref "IC2") (pin "RPWM") (pinfunction "RPWM_RPWM") (pintype "bidirectional"))
    )
    (net (code "69") (name "/PWM0") (class "Default")
      (node (ref "IC1") (pin "23") (pinfunction "(OC2A/PCINT4)PB4_23") (pintype "bidirectional"))
      (node (ref "PWM") (pin "1") (pinfunction "1_1") (pintype "passive"))
    )
    (net (code "70") (name "/PWM1") (class "Default")
      (node (ref "IC1") (pin "24") (pinfunction "(OC1A/PCINT5)PB5_24") (pintype "bidirectional"))
      (node (ref "PWM") (pin "2") (pinfunction "2_2") (pintype "passive"))
    )
    (net (code "71") (name "/PWM2") (class "Default")
      (node (ref "IC1") (pin "25") (pinfunction "(OC1B/PCINT6)PB6_25") (pintype "bidirectional"))
      (node (ref "PWM") (pin "3") (pinfunction "3_3") (pintype "passive"))
    )
    (net (code "72") (name "/PWM3") (class "Default")
      (node (ref "IC1") (pin "26") (pinfunction "(OC0A/OC1C/PCINT7)PB7_26") (pintype "bidirectional"))
      (node (ref "PWM") (pin "4") (pinfunction "4_4") (pintype "passive"))
    )
    (net (code "73") (name "/RESET") (class "Default")
      (node (ref "C7") (pin "2") (pinfunction "2_2") (pintype "passive"))
      (node (ref "IC1") (pin "30") (pinfunction "RESET_30") (pintype "input"))
      (node (ref "JTAG_ISP") (pin "6") (pinfunction "6_6") (pintype "passive"))
      (node (ref "R1") (pin "1") (pinfunction "1_1") (pintype "passive"))
      (node (ref "RESET") (pin "A2") (pinfunction "1_A2") (pintype "passive"))
      (node (ref "SPI_ISP") (pin "5") (pinfunction "5_5") (pintype "passive"))
    )
    (net (code "74") (name "/SERVO0") (class "Default")
      (node (ref "IC1") (pin "15") (pinfunction "PH3(OC4A)_15") (pintype "bidirectional"))
      (node (ref "SERVO_0") (pin "1") (pinfunction "1_1") (pintype "passive"))
    )
    (net (code "75") (name "/SERVO1") (class "Default")
      (node (ref "IC1") (pin "16") (pinfunction "PH4(OC4B)_16") (pintype "bidirectional"))
      (node (ref "SERVO_1") (pin "1") (pinfunction "1_1") (pintype "passive"))
    )
    (net (code "76") (name "/SERVO2") (class "Default")
      (node (ref "IC1") (pin "17") (pinfunction "PH5(OC4C)_17") (pintype "bidirectional"))
      (node (ref "SERVO_2") (pin "1") (pinfunction "1_1") (pintype "passive"))
    )
    (net (code "77") (name "/SERVO3") (class "Default")
      (node (ref "IC1") (pin "18") (pinfunction "PH6(OC2B)_18") (pintype "bidirectional"))
      (node (ref "SERVO_3") (pin "1") (pinfunction "1_1") (pintype "passive"))
    )
    (net (code "78") (name "/SPI_MISO") (class "Default")
      (node (ref "IC1") (pin "22") (pinfunction "(MISO/PCINT3)PB3_22") (pintype "bidirectional"))
      (node (ref "SPI") (pin "1") (pinfunction "1_1") (pintype "passive"))
      (node (ref "SPI_ISP") (pin "1") (pinfunction "1_1") (pintype "passive"))
    )
    (net (code "79") (name "/SPI_MOSI") (class "Default")
      (node (ref "IC1") (pin "21") (pinfunction "(MOSI/PCINT2)PB2_21") (pintype "bidirectional"))
      (node (ref "SPI") (pin "4") (pinfunction "4_4") (pintype "passive"))
      (node (ref "SPI_ISP") (pin "4") (pinfunction "4_4") (pintype "passive"))
    )
    (net (code "80") (name "/SPI_SCK") (class "Default")
      (node (ref "IC1") (pin "20") (pinfunction "(SCK/PCINT1)PB1_20") (pintype "bidirectional"))
      (node (ref "SPI") (pin "3") (pinfunction "3_3") (pintype "passive"))
      (node (ref "SPI_ISP") (pin "3") (pinfunction "3_3") (pintype "passive"))
    )
    (net (code "81") (name "/SPI_SS") (class "Default")
      (node (ref "IC1") (pin "19") (pinfunction "(SS/PCINT0)PB0_19") (pintype "bidirectional"))
      (node (ref "SPI") (pin "5") (pinfunction "5_5") (pintype "passive"))
    )
    (net (code "82") (name "/USART1_CPU_RX") (class "Default")
      (node (ref "CPU_USART") (pin "2") (pinfunction "2_2") (pintype "passive"))
      (node (ref "Q6") (pin "3") (pinfunction "D_3") (pintype "passive"))
      (node (ref "R19") (pin "1") (pinfunction "1_1") (pintype "passive"))
    )
    (net (code "83") (name "/USART1_CPU_RX_LV") (class "Default")
      (node (ref "CPU") (pin "5") (pinfunction "5_5") (pintype "passive"))
      (node (ref "Q6") (pin "2") (pinfunction "S_2") (pintype "passive"))
      (node (ref "R18") (pin "1") (pinfunction "1_1") (pintype "passive"))
    )
    (net (code "84") (name "/USART1_CPU_TX") (class "Default")
      (node (ref "CPU_USART") (pin "1") (pinfunction "1_1") (pintype "passive"))
      (node (ref "Q5") (pin "3") (pinfunction "D_3") (pintype "passive"))
      (node (ref "R17") (pin "1") (pinfunction "1_1") (pintype "passive"))
    )
    (net (code "85") (name "/USART1_CPU_TX_LV") (class "Default")
      (node (ref "CPU") (pin "6") (pinfunction "6_6") (pintype "passive"))
      (node (ref "Q5") (pin "2") (pinfunction "S_2") (pintype "passive"))
      (node (ref "R16") (pin "1") (pinfunction "1_1") (pintype "passive"))
    )
    (net (code "86") (name "/USART1_RX") (class "Default")
      (node (ref "IC1") (pin "45") (pinfunction "(RXD1/INT2)PD2_45") (pintype "bidirectional"))
      (node (ref "USART") (pin "4") (pinfunction "4_4") (pintype "passive"))
    )
    (net (code "87") (name "/USART1_TX") (class "Default")
      (node (ref "IC1") (pin "46") (pinfunction "(TXD1/INT3)PD3_46") (pintype "bidirectional"))
      (node (ref "USART") (pin "3") (pinfunction "3_3") (pintype "passive"))
    )
    (net (code "88") (name "/USART_CPU_RX") (class "Default")
      (node (ref "IC1") (pin "12") (pinfunction "PH0(RXD2)_12") (pintype "bidirectional"))
      (node (ref "Q3") (pin "3") (pinfunction "D_3") (pintype "passive"))
      (node (ref "R13") (pin "1") (pinfunction "1_1") (pintype "passive"))
    )
    (net (code "89") (name "/USART_CPU_RX_LV") (class "Default")
      (node (ref "CPU") (pin "8") (pinfunction "8_8") (pintype "passive"))
      (node (ref "Q3") (pin "2") (pinfunction "S_2") (pintype "passive"))
      (node (ref "R12") (pin "1") (pinfunction "1_1") (pintype "passive"))
    )
    (net (code "90") (name "/USART_CPU_TX") (class "Default")
      (node (ref "IC1") (pin "13") (pinfunction "PH1(TXD2)_13") (pintype "bidirectional"))
      (node (ref "Q2") (pin "3") (pinfunction "D_3") (pintype "passive"))
      (node (ref "R11") (pin "1") (pinfunction "1_1") (pintype "passive"))
    )
    (net (code "91") (name "/USART_CPU_TX_LV") (class "Default")
      (node (ref "CPU") (pin "7") (pinfunction "7_7") (pintype "passive"))
      (node (ref "Q2") (pin "2") (pinfunction "S_2") (pintype "passive"))
      (node (ref "R10") (pin "1") (pinfunction "1_1") (pintype "passive"))
    )
    (net (code "92") (name "/USART_DEBUG_RX") (class "Default")
      (node (ref "DEBUG_USART") (pin "2") (pinfunction "2_2") (pintype "passive"))
      (node (ref "IC1") (pin "63") (pinfunction "PJ0(RXD3/PCINT9)_63") (pintype "bidirectional"))
    )
    (net (code "93") (name "/USART_DEBUG_TX") (class "Default")
      (node (ref "DEBUG_USART") (pin "1") (pinfunction "1_1") (pintype "passive"))
      (node (ref "IC1") (pin "64") (pinfunction "PJ1(TXD3/PCINT10)_64") (pintype "bidirectional"))
    )
    (net (code "94") (name "/USART_GPS_RX") (class "Default")
      (node (ref "IC1") (pin "2") (pinfunction "(RXD0/PCIN8)PE0_2") (pintype "bidirectional"))
      (node (ref "IC10") (pin "9") (pinfunction "TX_9") (pintype "bidirectional"))
    )
    (net (code "95") (name "/USART_GPS_TX") (class "Default")
      (node (ref "IC1") (pin "3") (pinfunction "(TXD0)PE1_3") (pintype "bidirectional"))
      (node (ref "R48") (pin "1") (pinfunction "1_1") (pintype "passive"))
    )
    (net (code "96") (name "/VBAT") (class "Default")
      (node (ref "G1") (pin "+") (pinfunction "+_+") (pintype "passive"))
      (node (ref "IC10") (pin "4") (pinfunction "VBACKUP_4") (pintype "bidirectional"))
      (node (ref "VBAT") (pin "2") (pinfunction "2_2") (pintype "passive"))
    )
    (net (code "97") (name "GND") (class "Default")
      (node (ref "ANALOG_0") (pin "3") (pinfunction "3_3") (pintype "passive"))
      (node (ref "ANALOG_1") (pin "3") (pinfunction "3_3") (pintype "passive"))
      (node (ref "ANALOG_2") (pin "3") (pinfunction "3_3") (pintype "passive"))
      (node (ref "ANALOG_3") (pin "3") (pinfunction "3_3") (pintype "passive"))
      (node (ref "BATTERY") (pin "V-") (pinfunction "V-_V-") (pintype "bidirectional"))
      (node (ref "BATTERY_CEL") (pin "P$1") (pinfunction "1_P$1") (pintype "passive"))
      (node (ref "C1") (pin "1") (pinfunction "1_1") (pintype "passive"))
      (node (ref "C10") (pin "-") (pinfunction "-_-") (pintype "passive"))
      (node (ref "C13") (pin "1") (pinfunction "1_1") (pintype "passive"))
      (node (ref "C14") (pin "2") (pinfunction "2_2") (pintype "passive"))
      (node (ref "C15") (pin "2") (pinfunction "2_2") (pintype "passive"))
      (node (ref "C16") (pin "2") (pinfunction "2_2") (pintype "passive"))
      (node (ref "C17") (pin "-") (pinfunction "-_-") (pintype "passive"))
      (node (ref "C18") (pin "-") (pinfunction "-_-") (pintype "passive"))
      (node (ref "C19") (pin "P$2") (pinfunction "-_P$2") (pintype "passive"))
      (node (ref "C2") (pin "1") (pinfunction "1_1") (pintype "passive"))
      (node (ref "C20") (pin "P$2") (pinfunction "-_P$2") (pintype "passive"))
      (node (ref "C3") (pin "2") (pinfunction "2_2") (pintype "passive"))
      (node (ref "C4") (pin "2") (pinfunction "2_2") (pintype "passive"))
      (node (ref "C5") (pin "2") (pinfunction "2_2") (pintype "passive"))
      (node (ref "C6") (pin "1") (pinfunction "1_1") (pintype "passive"))
      (node (ref "C7") (pin "1") (pinfunction "1_1") (pintype "passive"))
      (node (ref "C8") (pin "2") (pinfunction "2_2") (pintype "passive"))
      (node (ref "C9") (pin "2") (pinfunction "2_2") (pintype "passive"))
      (node (ref "CPU") (pin "3") (pinfunction "3_3") (pintype "passive"))
      (node (ref "CPU_PWR") (pin "1") (pinfunction "1_1") (pintype "passive"))
      (node (ref "CPU_USART") (pin "3") (pinfunction "3_3") (pintype "passive"))
      (node (ref "DEBUG_USART") (pin "3") (pinfunction "3_3") (pintype "passive"))
      (node (ref "ENCODER_L") (pin "3") (pinfunction "3_3") (pintype "passive"))
      (node (ref "ENCODER_R") (pin "3") (pinfunction "3_3") (pintype "passive"))
      (node (ref "G1") (pin "-") (pinfunction "-_-") (pintype "passive"))
      (node (ref "I2C_1") (pin "2") (pinfunction "2_2") (pintype "passive"))
      (node (ref "I2C_2") (pin "2") (pinfunction "2_2") (pintype "passive"))
      (node (ref "IC1") (pin "11") (pinfunction "GND_11") (pintype "power_in"))
      (node (ref "IC1") (pin "32") (pinfunction "GND1_32") (pintype "power_in"))
      (node (ref "IC1") (pin "62") (pinfunction "GND2_62") (pintype "power_in"))
      (node (ref "IC1") (pin "81") (pinfunction "GND3_81") (pintype "power_in"))
      (node (ref "IC1") (pin "99") (pinfunction "AGND_99") (pintype "power_in"))
      (node (ref "IC10") (pin "12") (pinfunction "GND_12") (pintype "bidirectional"))
      (node (ref "IC10") (pin "19") (pinfunction "GND_19") (pintype "bidirectional"))
      (node (ref "IC10") (pin "3") (pinfunction "GND_3") (pintype "bidirectional"))
      (node (ref "IC10") (pin "8") (pinfunction "GND_8") (pintype "bidirectional"))
      (node (ref "IC11") (pin "7") (pinfunction "GND_7") (pintype "power_in"))
      (node (ref "IC11") (pin "9") (pinfunction "GND_9") (pintype "power_in"))
      (node (ref "IC2") (pin "GND") (pinfunction "GND_GND") (pintype "bidirectional"))
      (node (ref "IC3") (pin "GND") (pinfunction "GND_GND") (pintype "bidirectional"))
      (node (ref "IC4") (pin "GND") (pinfunction "GND_GND") (pintype "bidirectional"))
      (node (ref "IC4") (pin "V-") (pinfunction "V-_V-") (pintype "bidirectional"))
      (node (ref "IC5") (pin "GND") (pinfunction "GND_GND") (pintype "bidirectional"))
      (node (ref "IC5") (pin "V-") (pinfunction "V-_V-") (pintype "bidirectional"))
      (node (ref "IC6") (pin "GND") (pinfunction "GND_GND") (pintype "bidirectional"))
      (node (ref "IC6") (pin "V-") (pinfunction "V-_V-") (pintype "bidirectional"))
      (node (ref "IC7") (pin "GND") (pinfunction "GND_GND") (pintype "bidirectional"))
      (node (ref "IC8") (pin "GND") (pinfunction "GND_GND") (pintype "bidirectional"))
      (node (ref "IC9") (pin "1") (pinfunction "GND_1") (pintype "power_in"))
      (node (ref "J1") (pin "P$1") (pinfunction "GND_P$1") (pintype "bidirectional"))
      (node (ref "J1") (pin "P$2") (pinfunction "GND_P$2") (pintype "bidirectional"))
      (node (ref "JTAG_ISP") (pin "10") (pinfunction "10_10") (pintype "passive"))
      (node (ref "JTAG_ISP") (pin "2") (pinfunction "2_2") (pintype "passive"))
      (node (ref "KINECT_PWR") (pin "2") (pinfunction "2_2") (pintype "passive"))
      (node (ref "LED1") (pin "C") (pinfunction "C_C") (pintype "passive"))
      (node (ref "LED14") (pin "C") (pinfunction "C_C") (pintype "passive"))
      (node (ref "LED2") (pin "C") (pinfunction "C_C") (pintype "passive"))
      (node (ref "LED3") (pin "C") (pinfunction "C_C") (pintype "passive"))
      (node (ref "LED4") (pin "C") (pinfunction "C_C") (pintype "passive"))
      (node (ref "LED5") (pin "C") (pinfunction "C_C") (pintype "passive"))
      (node (ref "LED6") (pin "C") (pinfunction "C_C") (pintype "passive"))
      (node (ref "LED7") (pin "C") (pinfunction "C_C") (pintype "passive"))
      (node (ref "LED8") (pin "C") (pinfunction "C_C") (pintype "passive"))
      (node (ref "LED_+5V") (pin "C") (pinfunction "C_C") (pintype "passive"))
      (node (ref "LED_CPU") (pin "C") (pinfunction "C_C") (pintype "passive"))
      (node (ref "LED_KINECT") (pin "C") (pinfunction "C_C") (pintype "passive"))
      (node (ref "LED_MOTOR") (pin "C") (pinfunction "C_C") (pintype "passive"))
      (node (ref "LED_SERVO") (pin "C") (pinfunction "C_C") (pintype "passive"))
      (node (ref "Q10") (pin "2") (pinfunction "S_2") (pintype "passive"))
      (node (ref "Q11") (pin "2") (pinfunction "S_2") (pintype "passive"))
      (node (ref "Q9") (pin "2") (pinfunction "S_2") (pintype "passive"))
      (node (ref "R21") (pin "1") (pinfunction "1_1") (pintype "passive"))
      (node (ref "R23") (pin "1") (pinfunction "1_1") (pintype "passive"))
      (node (ref "R29") (pin "1") (pinfunction "1_1") (pintype "passive"))
      (node (ref "R30") (pin "1") (pinfunction "1_1") (pintype "passive"))
      (node (ref "R40") (pin "1") (pinfunction "1_1") (pintype "passive"))
      (node (ref "R41") (pin "1") (pinfunction "1_1") (pintype "passive"))
      (node (ref "R43") (pin "1") (pinfunction "1_1") (pintype "passive"))
      (node (ref "R45") (pin "1") (pinfunction "1_1") (pintype "passive"))
      (node (ref "R47") (pin "2") (pinfunction "2_2") (pintype "passive"))
      (node (ref "RESET") (pin "B2") (pinfunction "2_B2") (pintype "passive"))
      (node (ref "SERVO_0") (pin "3") (pinfunction "3_3") (pintype "passive"))
      (node (ref "SERVO_1") (pin "3") (pinfunction "3_3") (pintype "passive"))
      (node (ref "SERVO_2") (pin "3") (pinfunction "3_3") (pintype "passive"))
      (node (ref "SERVO_3") (pin "3") (pinfunction "3_3") (pintype "passive"))
      (node (ref "SG1") (pin "-") (pinfunction "2_-") (pintype "passive"))
      (node (ref "SPI") (pin "6") (pinfunction "6_6") (pintype "passive"))
      (node (ref "SPI_ISP") (pin "6") (pinfunction "6_6") (pintype "passive"))
      (node (ref "SWITCH") (pin "1") (pinfunction "1_1") (pintype "passive"))
      (node (ref "USART") (pin "2") (pinfunction "2_2") (pintype "passive"))
      (node (ref "VBAT") (pin "1") (pinfunction "1_1") (pintype "passive"))
    )
    (net (code "98") (name "Net-(BATTERY-PadV+)") (class "Default")
      (node (ref "BATTERY") (pin "V+") (pinfunction "V+_V+") (pintype "bidirectional"))
      (node (ref "IC8") (pin "V-") (pinfunction "V-_V-") (pintype "bidirectional"))
    )
    (net (code "99") (name "Net-(C8-Pad1)") (class "Default")
      (node (ref "C8") (pin "1") (pinfunction "1_1") (pintype "passive"))
      (node (ref "IC8") (pin "FILTER") (pinfunction "FILTER_FILTER") (pintype "bidirectional"))
    )
    (net (code "100") (name "Net-(C11-Pad2)") (class "Default")
      (node (ref "C11") (pin "2") (pinfunction "2_2") (pintype "passive"))
      (node (ref "R37") (pin "2") (pinfunction "2_2") (pintype "passive"))
    )
    (net (code "101") (name "Net-(C12-Pad2)") (class "Default")
      (node (ref "C12") (pin "2") (pinfunction "2_2") (pintype "passive"))
      (node (ref "R38") (pin "2") (pinfunction "2_2") (pintype "passive"))
    )
    (net (code "102") (name "Net-(CPU_PWR-Pad2)") (class "Default")
      (node (ref "CPU_PWR") (pin "2") (pinfunction "2_2") (pintype "passive"))
      (node (ref "IC4") (pin "VOUT") (pinfunction "VOUT_VOUT") (pintype "bidirectional"))
    )
    (net (code "103") (name "Net-(IC1-AREF)") (class "Default")
      (node (ref "C6") (pin "2") (pinfunction "2_2") (pintype "passive"))
      (node (ref "IC1") (pin "98") (pinfunction "AREF_98") (pintype "bidirectional"))
    )
    (net (code "104") (name "Net-(IC1-XTAL1)") (class "Default")
      (node (ref "C2") (pin "2") (pinfunction "2_2") (pintype "passive"))
      (node (ref "IC1") (pin "34") (pinfunction "XTAL1_34") (pintype "input"))
      (node (ref "Q1") (pin "P$1") (pinfunction "1_P$1") (pintype "passive"))
    )
    (net (code "105") (name "Net-(IC1-XTAL2)") (class "Default")
      (node (ref "C1") (pin "2") (pinfunction "2_2") (pintype "passive"))
      (node (ref "IC1") (pin "33") (pinfunction "XTAL2_33") (pintype "output"))
      (node (ref "Q1") (pin "P$2") (pinfunction "2_P$2") (pintype "passive"))
    )
    (net (code "106") (name "Net-(IC3-PadVOUT)") (class "Default")
      (node (ref "IC3") (pin "VOUT") (pinfunction "VOUT_VOUT") (pintype "bidirectional"))
      (node (ref "KINECT_PWR") (pin "1") (pinfunction "1_1") (pintype "passive"))
    )
    (net (code "107") (name "Net-(IC6-PadEN)") (class "Default")
      (node (ref "IC6") (pin "EN") (pinfunction "EN_EN") (pintype "bidirectional"))
      (node (ref "SWITCH") (pin "2") (pinfunction "2_2") (pintype "passive"))
    )
    (net (code "108") (name "Net-(IC10-3D-FIX)") (class "Default")
      (node (ref "IC10") (pin "5") (pinfunction "3D-FIX_5") (pintype "bidirectional"))
      (node (ref "R50") (pin "2") (pinfunction "2_2") (pintype "passive"))
    )
    (net (code "109") (name "Net-(IC10-EXT_ANT)") (class "Default")
      (node (ref "IC10") (pin "11") (pinfunction "EXT_ANT_11") (pintype "bidirectional"))
      (node (ref "J1") (pin "P$3") (pinfunction "SIGNAL_P$3") (pintype "bidirectional"))
    )
    (net (code "110") (name "Net-(IC10-RX)") (class "Default")
      (node (ref "IC10") (pin "10") (pinfunction "RX_10") (pintype "bidirectional"))
      (node (ref "R47") (pin "1") (pinfunction "1_1") (pintype "passive"))
      (node (ref "R48") (pin "2") (pinfunction "2_2") (pintype "passive"))
    )
    (net (code "111") (name "Net-(IC11-IN+)") (class "Default")
      (node (ref "IC11") (pin "3") (pinfunction "IN+_3") (pintype "bidirectional"))
      (node (ref "R37") (pin "1") (pinfunction "1_1") (pintype "passive"))
    )
    (net (code "112") (name "Net-(IC11-IN-)") (class "Default")
      (node (ref "IC11") (pin "4") (pinfunction "IN-_4") (pintype "bidirectional"))
      (node (ref "R38") (pin "1") (pinfunction "1_1") (pintype "passive"))
    )
    (net (code "113") (name "Net-(IC11-OUT+)") (class "Default")
      (node (ref "IC11") (pin "5") (pinfunction "OUT+_5") (pintype "bidirectional"))
      (node (ref "SPEAKER") (pin "1") (pinfunction "1_1") (pintype "passive"))
    )
    (net (code "114") (name "Net-(IC11-OUT-)") (class "Default")
      (node (ref "IC11") (pin "8") (pinfunction "OUT-_8") (pintype "bidirectional"))
      (node (ref "SPEAKER") (pin "2") (pinfunction "2_2") (pintype "passive"))
    )
    (net (code "115") (name "Net-(LED1-PadA)") (class "Default")
      (node (ref "LED1") (pin "A") (pinfunction "A_A") (pintype "passive"))
      (node (ref "R2") (pin "1") (pinfunction "1_1") (pintype "passive"))
    )
    (net (code "116") (name "Net-(LED2-PadA)") (class "Default")
      (node (ref "LED2") (pin "A") (pinfunction "A_A") (pintype "passive"))
      (node (ref "R3") (pin "1") (pinfunction "1_1") (pintype "passive"))
    )
    (net (code "117") (name "Net-(LED3-PadA)") (class "Default")
      (node (ref "LED3") (pin "A") (pinfunction "A_A") (pintype "passive"))
      (node (ref "R4") (pin "1") (pinfunction "1_1") (pintype "passive"))
    )
    (net (code "118") (name "Net-(LED4-PadA)") (class "Default")
      (node (ref "LED4") (pin "A") (pinfunction "A_A") (pintype "passive"))
      (node (ref "R5") (pin "1") (pinfunction "1_1") (pintype "passive"))
    )
    (net (code "119") (name "Net-(LED5-PadA)") (class "Default")
      (node (ref "LED5") (pin "A") (pinfunction "A_A") (pintype "passive"))
      (node (ref "R6") (pin "1") (pinfunction "1_1") (pintype "passive"))
    )
    (net (code "120") (name "Net-(LED6-PadA)") (class "Default")
      (node (ref "LED6") (pin "A") (pinfunction "A_A") (pintype "passive"))
      (node (ref "R7") (pin "1") (pinfunction "1_1") (pintype "passive"))
    )
    (net (code "121") (name "Net-(LED7-PadA)") (class "Default")
      (node (ref "LED7") (pin "A") (pinfunction "A_A") (pintype "passive"))
      (node (ref "R8") (pin "1") (pinfunction "1_1") (pintype "passive"))
    )
    (net (code "122") (name "Net-(LED8-PadA)") (class "Default")
      (node (ref "LED8") (pin "A") (pinfunction "A_A") (pintype "passive"))
      (node (ref "R9") (pin "1") (pinfunction "1_1") (pintype "passive"))
    )
    (net (code "123") (name "Net-(LED14-PadA)") (class "Default")
      (node (ref "LED14") (pin "A") (pinfunction "A_A") (pintype "passive"))
      (node (ref "R50") (pin "1") (pinfunction "1_1") (pintype "passive"))
    )
    (net (code "124") (name "Net-(LED_+5V-PadA)") (class "Default")
      (node (ref "LED_+5V") (pin "A") (pinfunction "A_A") (pintype "passive"))
      (node (ref "R24") (pin "1") (pinfunction "1_1") (pintype "passive"))
    )
    (net (code "125") (name "Net-(LED_CPU-PadA)") (class "Default")
      (node (ref "LED_CPU") (pin "A") (pinfunction "A_A") (pintype "passive"))
      (node (ref "R26") (pin "1") (pinfunction "1_1") (pintype "passive"))
    )
    (net (code "126") (name "Net-(LED_KINECT-PadA)") (class "Default")
      (node (ref "LED_KINECT") (pin "A") (pinfunction "A_A") (pintype "passive"))
      (node (ref "R28") (pin "1") (pinfunction "1_1") (pintype "passive"))
    )
    (net (code "127") (name "Net-(LED_MOTOR-PadA)") (class "Default")
      (node (ref "LED_MOTOR") (pin "A") (pinfunction "A_A") (pintype "passive"))
      (node (ref "R27") (pin "1") (pinfunction "1_1") (pintype "passive"))
    )
    (net (code "128") (name "Net-(LED_SERVO-PadA)") (class "Default")
      (node (ref "LED_SERVO") (pin "A") (pinfunction "A_A") (pintype "passive"))
      (node (ref "R25") (pin "1") (pinfunction "1_1") (pintype "passive"))
    )
    (net (code "129") (name "Net-(Q7-G)") (class "Default")
      (node (ref "Q7") (pin "1") (pinfunction "G_1") (pintype "passive"))
      (node (ref "R33") (pin "1") (pinfunction "1_1") (pintype "passive"))
      (node (ref "R34") (pin "2") (pinfunction "2_2") (pintype "passive"))
    )
    (net (code "130") (name "Net-(Q8-G)") (class "Default")
      (node (ref "Q8") (pin "1") (pinfunction "G_1") (pintype "passive"))
      (node (ref "R31") (pin "1") (pinfunction "1_1") (pintype "passive"))
      (node (ref "R32") (pin "2") (pinfunction "2_2") (pintype "passive"))
    )
    (net (code "131") (name "Net-(Q9-D)") (class "Default")
      (node (ref "LIGHTS0") (pin "2") (pinfunction "2_2") (pintype "passive"))
      (node (ref "Q9") (pin "3") (pinfunction "D_3") (pintype "passive"))
    )
    (net (code "132") (name "Net-(Q9-G)") (class "Default")
      (node (ref "Q9") (pin "1") (pinfunction "G_1") (pintype "passive"))
      (node (ref "R41") (pin "2") (pinfunction "2_2") (pintype "passive"))
      (node (ref "R42") (pin "1") (pinfunction "1_1") (pintype "passive"))
    )
    (net (code "133") (name "Net-(Q10-D)") (class "Default")
      (node (ref "LIGHTS1") (pin "2") (pinfunction "2_2") (pintype "passive"))
      (node (ref "Q10") (pin "3") (pinfunction "D_3") (pintype "passive"))
    )
    (net (code "134") (name "Net-(Q10-G)") (class "Default")
      (node (ref "Q10") (pin "1") (pinfunction "G_1") (pintype "passive"))
      (node (ref "R43") (pin "2") (pinfunction "2_2") (pintype "passive"))
      (node (ref "R44") (pin "1") (pinfunction "1_1") (pintype "passive"))
    )
    (net (code "135") (name "Net-(Q11-D)") (class "Default")
      (node (ref "LIGHTS2") (pin "2") (pinfunction "2_2") (pintype "passive"))
      (node (ref "Q11") (pin "3") (pinfunction "D_3") (pintype "passive"))
    )
    (net (code "136") (name "Net-(Q11-G)") (class "Default")
      (node (ref "Q11") (pin "1") (pinfunction "G_1") (pintype "passive"))
      (node (ref "R45") (pin "2") (pinfunction "2_2") (pintype "passive"))
      (node (ref "R46") (pin "1") (pinfunction "1_1") (pintype "passive"))
    )
    (net (code "137") (name "Net-(R39-S)") (class "Default")
      (node (ref "C11") (pin "1") (pinfunction "1_1") (pintype "passive"))
      (node (ref "R39") (pin "2") (pinfunction "S_2") (pintype "passive"))
    )
    (net (code "138") (name "V+") (class "Default")
      (node (ref "C10") (pin "+") (pinfunction "+_+") (pintype "passive"))
      (node (ref "C17") (pin "+") (pinfunction "+_+") (pintype "passive"))
      (node (ref "C18") (pin "+") (pinfunction "+_+") (pintype "passive"))
      (node (ref "C19") (pin "P$1") (pinfunction "+_P$1") (pintype "passive"))
      (node (ref "C20") (pin "P$1") (pinfunction "+_P$1") (pintype "passive"))
      (node (ref "IC2") (pin "+12V") (pinfunction "+12V_+12V") (pintype "bidirectional"))
      (node (ref "IC4") (pin "V+") (pinfunction "V+_V+") (pintype "bidirectional"))
      (node (ref "IC5") (pin "V+") (pinfunction "V+_V+") (pintype "bidirectional"))
      (node (ref "IC6") (pin "V+") (pinfunction "V+_V+") (pintype "bidirectional"))
      (node (ref "IC8") (pin "V+") (pinfunction "V+_V+") (pintype "bidirectional"))
      (node (ref "Q7") (pin "2") (pinfunction "S_2") (pintype "passive"))
    )
    (net (code "139") (name "unconnected-(G1-+-Pad+@1)") (class "Default")
      (node (ref "G1") (pin "+@1") (pinfunction "+_+@1") (pintype "passive"))
    )
    (net (code "140") (name "unconnected-(IC1-(ALE)PG2-Pad70)") (class "Default")
      (node (ref "IC1") (pin "70") (pinfunction "(ALE)PG2_70") (pintype "bidirectional"))
    )
    (net (code "141") (name "unconnected-(IC1-(T0)PD7-Pad50)") (class "Default")
      (node (ref "IC1") (pin "50") (pinfunction "(T0)PD7_50") (pintype "bidirectional"))
    )
    (net (code "142") (name "unconnected-(IC1-(T1)PD6-Pad49)") (class "Default")
      (node (ref "IC1") (pin "49") (pinfunction "(T1)PD6_49") (pintype "bidirectional"))
    )
    (net (code "143") (name "unconnected-(IC1-(TOSC1)PG4-Pad29)") (class "Default")
      (node (ref "IC1") (pin "29") (pinfunction "(TOSC1)PG4_29") (pintype "bidirectional"))
    )
    (net (code "144") (name "unconnected-(IC1-(TOSC2)PG3-Pad28)") (class "Default")
      (node (ref "IC1") (pin "28") (pinfunction "(TOSC2)PG3_28") (pintype "bidirectional"))
    )
    (net (code "145") (name "unconnected-(IC1-(WR)PG0-Pad51)") (class "Default")
      (node (ref "IC1") (pin "51") (pinfunction "(WR)PG0_51") (pintype "bidirectional"))
    )
    (net (code "146") (name "unconnected-(IC1-PH7(T4)-Pad27)") (class "Default")
      (node (ref "IC1") (pin "27") (pinfunction "PH7(T4)_27") (pintype "bidirectional"))
    )
    (net (code "147") (name "unconnected-(IC1-PJ2(XCK3{slash}PCINT11)-Pad65)") (class "Default")
      (node (ref "IC1") (pin "65") (pinfunction "PJ2(XCK3/PCINT11)_65") (pintype "bidirectional"))
    )
    (net (code "148") (name "unconnected-(IC1-PJ7-Pad79)") (class "Default")
      (node (ref "IC1") (pin "79") (pinfunction "PJ7_79") (pintype "bidirectional"))
    )
    (net (code "149") (name "unconnected-(IC7-PadVDD)") (class "Default")
      (node (ref "IC7") (pin "VDD") (pinfunction "VDD_VDD") (pintype "bidirectional"))
    )
    (net (code "150") (name "unconnected-(IC10-1PPS-Pad13)") (class "Default")
      (node (ref "IC10") (pin "13") (pinfunction "1PPS_13") (pintype "bidirectional"))
    )
    (net (code "151") (name "unconnected-(IC10-NC-Pad6)") (class "Default")
      (node (ref "IC10") (pin "6") (pinfunction "NC_6") (pintype "bidirectional"))
    )
    (net (code "152") (name "unconnected-(IC10-NC-Pad7)") (class "Default")
      (node (ref "IC10") (pin "7") (pinfunction "NC_7") (pintype "bidirectional"))
    )
    (net (code "153") (name "unconnected-(IC10-NC-Pad15)") (class "Default")
      (node (ref "IC10") (pin "15") (pinfunction "NC_15") (pintype "bidirectional"))
    )
    (net (code "154") (name "unconnected-(IC10-NC-Pad16)") (class "Default")
      (node (ref "IC10") (pin "16") (pinfunction "NC_16") (pintype "bidirectional"))
    )
    (net (code "155") (name "unconnected-(IC10-NC-Pad17)") (class "Default")
      (node (ref "IC10") (pin "17") (pinfunction "NC_17") (pintype "bidirectional"))
    )
    (net (code "156") (name "unconnected-(IC10-NC-Pad18)") (class "Default")
      (node (ref "IC10") (pin "18") (pinfunction "NC_18") (pintype "bidirectional"))
    )
    (net (code "157") (name "unconnected-(IC10-NC-Pad20)") (class "Default")
      (node (ref "IC10") (pin "20") (pinfunction "NC_20") (pintype "bidirectional"))
    )
    (net (code "158") (name "unconnected-(IC10-RTCM-Pad14)") (class "Default")
      (node (ref "IC10") (pin "14") (pinfunction "RTCM_14") (pintype "bidirectional"))
    )
    (net (code "159") (name "unconnected-(JTAG_ISP-Pad7)") (class "Default")
      (node (ref "JTAG_ISP") (pin "7") (pinfunction "7_7") (pintype "passive"))
    )
    (net (code "160") (name "unconnected-(JTAG_ISP-Pad8)") (class "Default")
      (node (ref "JTAG_ISP") (pin "8") (pinfunction "8_8") (pintype "passive"))
    )
  )
)
